# Board_Power.net
KiCad netlist of a schematic drawn in Altium Designer
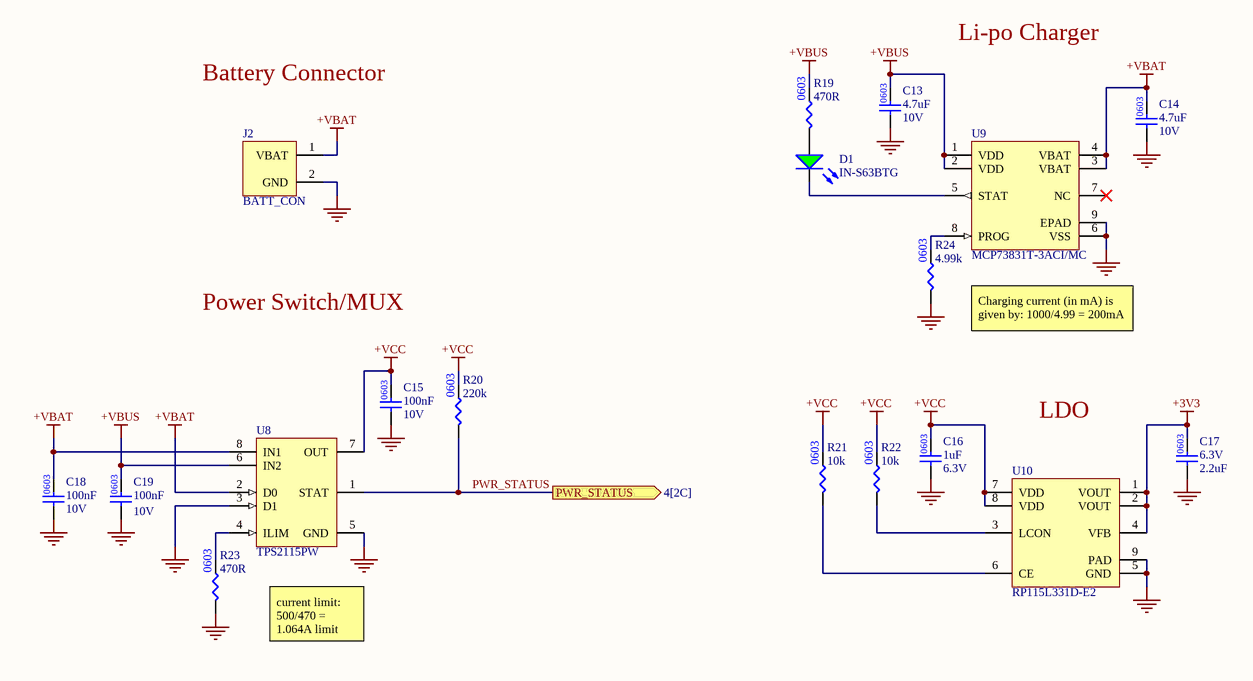
[diagram p0: Board_Power.SchDoc]

(export (version "E")
  (design (tool "Eeschema 10.0.6"))
  (components
    (comp (ref "C13")
      (value "CL10A475KP8NNNC")
      (footprint "CAP_0603")
      (description "CAP CER 4.7UF 10V X5R 0603")
      (fields
        (field (name "MANUFACTURER") "Samsung")
        (field (name "TOLERANCE") "10%")
        (field (name "CAPACITANCE") "4.7uF")
        (field (name "VOLTAGE RATING") "10V")
      )
      (libsource (lib "Smartwatch_Lib") (part "CL10A475KP8NNNC"))
    )
    (comp (ref "C14")
      (value "CL10A475KP8NNNC")
      (footprint "CAP_0603")
      (description "CAP CER 4.7UF 10V X5R 0603")
      (fields
        (field (name "MANUFACTURER") "Samsung")
        (field (name "TOLERANCE") "10%")
        (field (name "CAPACITANCE") "4.7uF")
        (field (name "VOLTAGE RATING") "10V")
      )
      (libsource (lib "Smartwatch_Lib") (part "CL10A475KP8NNNC"))
    )
    (comp (ref "C15")
      (value "CC0603KRX7R6BB104")
      (footprint "CAP_0603")
      (description "CAP CER 0.1UF 10V X7R 0603")
      (fields
        (field (name "MANUFACTURER") "Yageo")
        (field (name "TOLERANCE") "10%")
        (field (name "CAPACITANCE") "100nF")
        (field (name "VOLTAGE RATING") "10V")
      )
      (libsource (lib "Smartwatch_Lib") (part "CC0603KRX7R6BB104"))
    )
    (comp (ref "C16")
      (value "CL10A105KQ8NNNC")
      (footprint "CAP_0603")
      (description "CAP CER 1UF 6.3V X5R 0603")
      (fields
        (field (name "MANUFACTURER") "Samsung")
        (field (name "TOLERANCE") "10%")
        (field (name "CAPACITANCE") "1uF")
        (field (name "VOLTAGE RATING (DC)") "6.3V")
      )
      (libsource (lib "Smartwatch_Lib") (part "CL10A105KQ8NNNC"))
    )
    (comp (ref "C17")
      (value "CL10A225KQ8NNNC")
      (footprint "CAP_0603")
      (description "CAP CER 2.2UF 6.3V X5R 0603")
      (fields
        (field (name "MANUFACTURER") "Samsung")
        (field (name "TOLERANCE") "10%")
        (field (name "VOLTAGE RATING") "6.3V")
        (field (name "CAPACITANCE") "2.2uF")
      )
      (libsource (lib "Smartwatch_Lib") (part "CL10A225KQ8NNNC"))
    )
    (comp (ref "C18")
      (value "CC0603KRX7R6BB104")
      (footprint "CAP_0603")
      (description "CAP CER 0.1UF 10V X7R 0603")
      (fields
        (field (name "MANUFACTURER") "Yageo")
        (field (name "TOLERANCE") "10%")
        (field (name "CAPACITANCE") "100nF")
        (field (name "VOLTAGE RATING") "10V")
      )
      (libsource (lib "Smartwatch_Lib") (part "CC0603KRX7R6BB104"))
    )
    (comp (ref "C19")
      (value "CC0603KRX7R6BB104")
      (footprint "CAP_0603")
      (description "CAP CER 0.1UF 10V X7R 0603")
      (fields
        (field (name "MANUFACTURER") "Yageo")
        (field (name "TOLERANCE") "10%")
        (field (name "CAPACITANCE") "100nF")
        (field (name "VOLTAGE RATING") "10V")
      )
      (libsource (lib "Smartwatch_Lib") (part "CC0603KRX7R6BB104"))
    )
    (comp (ref "D1")
      (value "IN-S63BTG")
      (footprint "LED_0603")
      (description "LED Uni-Color Green 530nm 2-Pin Chip 0603(1608Metric) T/R")
      (fields (field (name "MANUFACTURER") "Inolux"))
      (libsource (lib "Smartwatch_Lib") (part "IN-S63BTG"))
    )
    (comp (ref "J2")
      (value "BATT_CON")
      (footprint "BATT_CON")
      (description "Pads for Battery Connection")
      (libsource (lib "Smartwatch_Lib") (part "BATT_CON"))
    )
    (comp (ref "R19")
      (value "RC0603FR-07470RL")
      (footprint "RES_0603")
      (description "RES 470 OHM 1% 1/10W 0603")
      (fields
        (field (name "MANUFACTURER") "Yageo")
        (field (name "TOLERANCE") "1%")
        (field (name "RESISTANCE") "470R")
      )
      (libsource (lib "Smartwatch_Lib") (part "RC0603FR-07470RL"))
    )
    (comp (ref "R20")
      (value "RMCF0603FT220K")
      (footprint "RES_0603")
      (description "Res Thick Film 0603 220K Ohm 1% 0.1W(1/10W) ±100ppm/C Pad SMD Automotive T/R")
      (fields
        (field (name "MANUFACTURER") "Stackpole Electronics")
        (field (name "TOLERANCE") "1%")
        (field (name "RESISTANCE") "220k")
      )
      (libsource (lib "Smartwatch_Lib") (part "RMCF0603FT220K"))
    )
    (comp (ref "R21")
      (value "RNCP0603FTD10K0")
      (footprint "RES_0603")
      (description "Res Thin Film 0603 10K Ohm 1% 1/8W ±100ppm/°C Molded SMD SMD Paper T/R")
      (fields
        (field (name "MANUFACTURER") "Stackpole Electronics")
        (field (name "TOLERANCE") "1%")
        (field (name "RESISTANCE") "10k")
      )
      (libsource (lib "Smartwatch_Lib") (part "RNCP0603FTD10K0"))
    )
    (comp (ref "R22")
      (value "RNCP0603FTD10K0")
      (footprint "RES_0603")
      (description "Res Thin Film 0603 10K Ohm 1% 1/8W ±100ppm/°C Molded SMD SMD Paper T/R")
      (fields
        (field (name "MANUFACTURER") "Stackpole Electronics")
        (field (name "TOLERANCE") "1%")
        (field (name "RESISTANCE") "10k")
      )
      (libsource (lib "Smartwatch_Lib") (part "RNCP0603FTD10K0"))
    )
    (comp (ref "R23")
      (value "RC0603FR-07470RL")
      (footprint "RES_0603")
      (description "RES 470 OHM 1% 1/10W 0603")
      (fields
        (field (name "MANUFACTURER") "Yageo")
        (field (name "TOLERANCE") "1%")
        (field (name "RESISTANCE") "470R")
      )
      (libsource (lib "Smartwatch_Lib") (part "RC0603FR-07470RL"))
    )
    (comp (ref "R24")
      (value "RC0603FR-074K99L")
      (footprint "RES_0603")
      (description "RES 4.99K OHM 1% 1/10W 0603")
      (fields
        (field (name "MANUFACTURER") "Yageo")
        (field (name "TOLERANCE") "1%")
        (field (name "RESISTANCE") "4.99k")
      )
      (libsource (lib "Smartwatch_Lib") (part "RC0603FR-074K99L"))
    )
    (comp (ref "U8")
      (value "TPS2115PW")
      (footprint "TPS2115PW")
      (description "Pwr Mux Autoswitch 1.5V to 5.5V 1.25A 8-Pin TSSOP Tube")
      (fields (field (name "MANUFACTURER") "Texas Instruments"))
      (libsource (lib "Smartwatch_Lib") (part "TPS2115PW"))
    )
    (comp (ref "U9")
      (value "MCP73831T-3ACI/MC")
      (footprint "MCP73831T-3ACI/MC")
      (description "Battery Management - Advanced Lithium-Ion/-Polymer Charge mgnt contr")
      (fields (field (name "MANUFACTURER") "Microchip"))
      (libsource (lib "Smartwatch_Lib") (part "MCP73831T-3ACI/MC"))
    )
    (comp (ref "U10")
      (value "RP115L331D-E2")
      (footprint "RP115L331D-E2")
      (description "LDO Regulator Pos 3.3V 0.5A/1A 8-Pin DFN EP T/R")
      (fields (field (name "MANUFACTURER") "Ricoh"))
      (libsource (lib "Smartwatch_Lib") (part "RP115L331D-E2"))
    )
  )
  (nets
    (net (code "1") (name "+3V3") (class "Default")
      (node (ref "C17") (pin "2") (pinfunction "2_2") (pintype "passive"))
      (node (ref "U10") (pin "1") (pinfunction "VOUT_1") (pintype "passive"))
      (node (ref "U10") (pin "2") (pinfunction "VOUT_2") (pintype "passive"))
      (node (ref "U10") (pin "4") (pinfunction "VFB_4") (pintype "passive"))
    )
    (net (code "2") (name "+VBAT") (class "Default")
      (node (ref "C14") (pin "2") (pinfunction "2_2") (pintype "passive"))
      (node (ref "C18") (pin "2") (pinfunction "2_2") (pintype "passive"))
      (node (ref "J2") (pin "1") (pinfunction "VBAT_1") (pintype "passive"))
      (node (ref "U8") (pin "2") (pinfunction "D0_2") (pintype "input"))
      (node (ref "U8") (pin "8") (pinfunction "IN1_8") (pintype "power_in"))
      (node (ref "U9") (pin "3") (pinfunction "VBAT_3") (pintype "passive"))
      (node (ref "U9") (pin "4") (pinfunction "VBAT_4") (pintype "passive"))
    )
    (net (code "3") (name "+VBUS") (class "Default")
      (node (ref "C13") (pin "2") (pinfunction "2_2") (pintype "passive"))
      (node (ref "C19") (pin "2") (pinfunction "2_2") (pintype "passive"))
      (node (ref "R19") (pin "2") (pinfunction "2_2") (pintype "passive"))
      (node (ref "U8") (pin "6") (pinfunction "IN2_6") (pintype "power_in"))
      (node (ref "U9") (pin "1") (pinfunction "VDD_1") (pintype "passive"))
      (node (ref "U9") (pin "2") (pinfunction "VDD_2") (pintype "passive"))
    )
    (net (code "4") (name "+VCC") (class "Default")
      (node (ref "C15") (pin "2") (pinfunction "2_2") (pintype "passive"))
      (node (ref "C16") (pin "2") (pinfunction "2_2") (pintype "passive"))
      (node (ref "R20") (pin "2") (pinfunction "2_2") (pintype "passive"))
      (node (ref "R21") (pin "2") (pinfunction "2_2") (pintype "passive"))
      (node (ref "R22") (pin "2") (pinfunction "2_2") (pintype "passive"))
      (node (ref "U10") (pin "7") (pinfunction "VDD_7") (pintype "passive"))
      (node (ref "U10") (pin "8") (pinfunction "VDD_8") (pintype "passive"))
      (node (ref "U8") (pin "7") (pinfunction "OUT_7") (pintype "power_in"))
    )
    (net (code "5") (name "/PWR_STATUS") (class "Default")
      (node (ref "R20") (pin "1") (pinfunction "1_1") (pintype "passive"))
      (node (ref "U8") (pin "1") (pinfunction "STAT_1") (pintype "tri_state"))
    )
    (net (code "6") (name "GND") (class "Default")
      (node (ref "C13") (pin "1") (pinfunction "1_1") (pintype "passive"))
      (node (ref "C14") (pin "1") (pinfunction "1_1") (pintype "passive"))
      (node (ref "C15") (pin "1") (pinfunction "1_1") (pintype "passive"))
      (node (ref "C16") (pin "1") (pinfunction "1_1") (pintype "passive"))
      (node (ref "C17") (pin "1") (pinfunction "1_1") (pintype "passive"))
      (node (ref "C18") (pin "1") (pinfunction "1_1") (pintype "passive"))
      (node (ref "C19") (pin "1") (pinfunction "1_1") (pintype "passive"))
      (node (ref "J2") (pin "2") (pinfunction "GND_2") (pintype "passive"))
      (node (ref "R23") (pin "1") (pinfunction "1_1") (pintype "passive"))
      (node (ref "R24") (pin "1") (pinfunction "1_1") (pintype "passive"))
      (node (ref "U10") (pin "5") (pinfunction "GND_5") (pintype "passive"))
      (node (ref "U10") (pin "9") (pinfunction "PAD_9") (pintype "passive"))
      (node (ref "U8") (pin "3") (pinfunction "D1_3") (pintype "input"))
      (node (ref "U8") (pin "5") (pinfunction "GND_5") (pintype "power_in"))
      (node (ref "U9") (pin "6") (pinfunction "VSS_6") (pintype "passive"))
      (node (ref "U9") (pin "9") (pinfunction "EPAD_9") (pintype "passive"))
    )
    (net (code "7") (name "Net-(D1-A)") (class "Default")
      (node (ref "D1") (pin "1") (pinfunction "A_1") (pintype "passive"))
      (node (ref "R19") (pin "1") (pinfunction "1_1") (pintype "passive"))
    )
    (net (code "8") (name "Net-(D1-K)") (class "Default")
      (node (ref "D1") (pin "2") (pinfunction "K_2") (pintype "passive"))
      (node (ref "U9") (pin "5") (pinfunction "STAT_5") (pintype "output"))
    )
    (net (code "9") (name "Net-(U8-ILIM)") (class "Default")
      (node (ref "R23") (pin "2") (pinfunction "2_2") (pintype "passive"))
      (node (ref "U8") (pin "4") (pinfunction "ILIM_4") (pintype "input"))
    )
    (net (code "10") (name "Net-(U9-PROG)") (class "Default")
      (node (ref "R24") (pin "2") (pinfunction "2_2") (pintype "passive"))
      (node (ref "U9") (pin "8") (pinfunction "PROG_8") (pintype "input"))
    )
    (net (code "11") (name "Net-(U10-CE)") (class "Default")
      (node (ref "R21") (pin "1") (pinfunction "1_1") (pintype "passive"))
      (node (ref "U10") (pin "6") (pinfunction "CE_6") (pintype "passive"))
    )
    (net (code "12") (name "Net-(U10-LCON)") (class "Default")
      (node (ref "R22") (pin "1") (pinfunction "1_1") (pintype "passive"))
      (node (ref "U10") (pin "3") (pinfunction "LCON_3") (pintype "passive"))
    )
    (net (code "13") (name "unconnected-(U9-NC-Pad7)") (class "Default")
      (node (ref "U9") (pin "7") (pinfunction "NC_7") (pintype "passive+no_connect"))
    )
  )
)
